# safety_assistant_sch.net
KiCad netlist of a schematic drawn in EAGLE
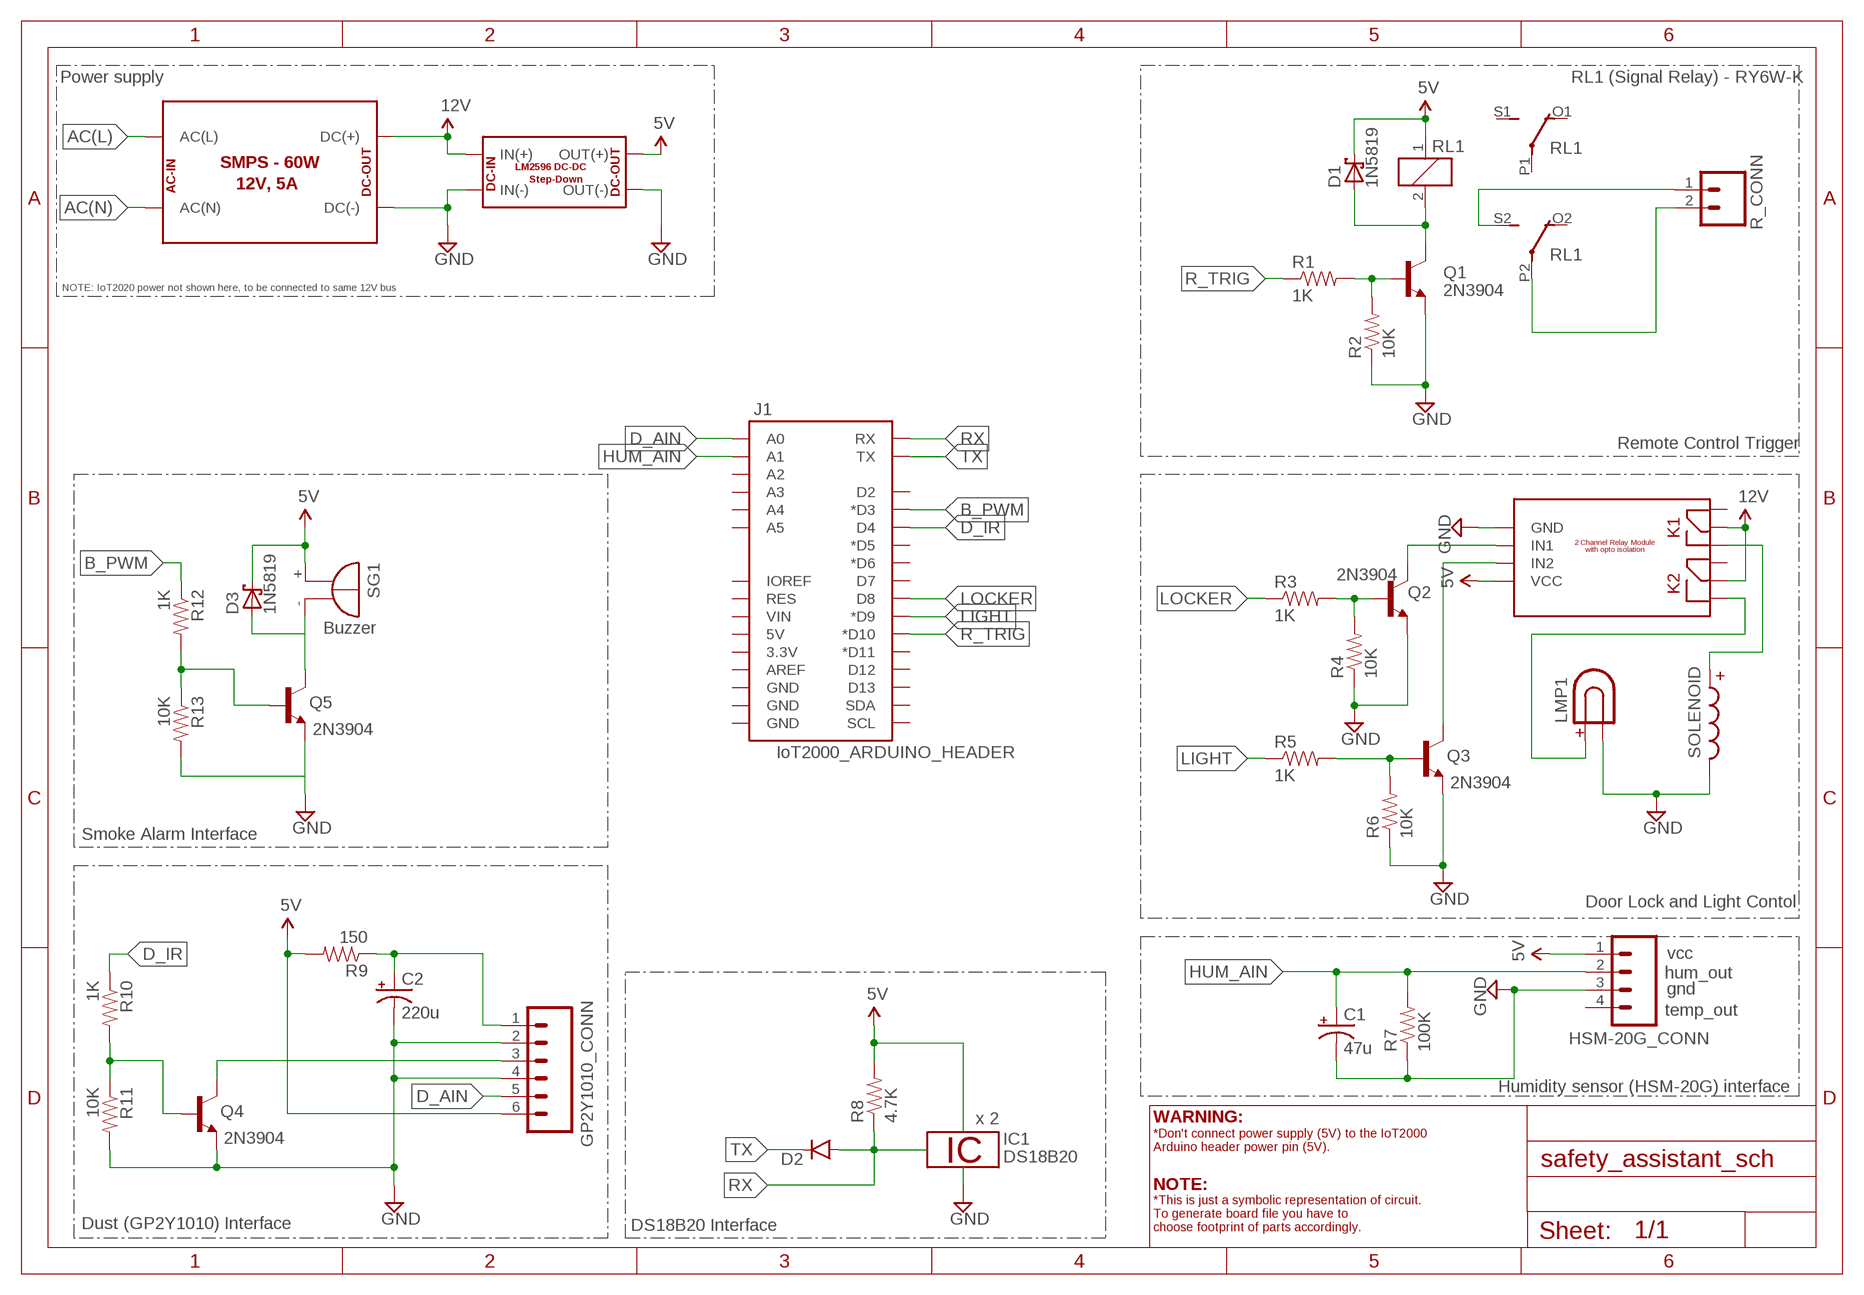
[diagram p0: schematic, sheet 1]

(export (version "E")
  (design (tool "Eeschema 10.0.6"))
  (components
    (comp (ref "C1")
      (value "47u")
      (footprint "eagle-import:CPOL-RADIAL-100UF-25V")
      (libsource (lib "eagle-import") (part "CAP_POLPTH1"))
    )
    (comp (ref "C2")
      (value "220u")
      (footprint "eagle-import:CPOL-RADIAL-100UF-25V")
      (libsource (lib "eagle-import") (part "CAP_POLPTH1"))
    )
    (comp (ref "D1")
      (value "1N5819")
      (footprint "eagle-import:DO41-7.6")
      (libsource (lib "eagle-import") (part "1N5819-B"))
    )
    (comp (ref "D2")
      (value "DIODE1N4148")
      (footprint "eagle-import:DIODE-1N4148")
      (libsource (lib "eagle-import") (part "DIODE1N4148"))
    )
    (comp (ref "D3")
      (value "1N5819")
      (footprint "eagle-import:DO41-7.6")
      (libsource (lib "eagle-import") (part "1N5819-B"))
    )
    (comp (ref "GP2Y1010_CONN")
      (value "M06SILK_FEMALE_PTH")
      (footprint "eagle-import:1X06")
      (libsource (lib "eagle-import") (part "M06SILK_FEMALE_PTH"))
    )
    (comp (ref "HSM-20G_CONN")
      (value "M04POLAR")
      (footprint "eagle-import:MOLEX-1X4")
      (libsource (lib "eagle-import") (part "M04POLAR"))
    )
    (comp (ref "IC1")
      (value "DS18B20")
      (footprint "eagle-import:TO92-")
      (libsource (lib "eagle-import") (part "DS18S20"))
    )
    (comp (ref "J1")
      (value "IoT2000_ARDUINO_HEADER")
      (footprint "eagle-import:UNO_R3_SHIELD")
      (libsource (lib "eagle-import") (part "ARDUINO_R3_SHIELD"))
    )
    (comp (ref "LMP1")
      (value "LAMP")
      (footprint "eagle-import:LDH-5R")
      (libsource (lib "eagle-import") (part "LAMP"))
    )
    (comp (ref "Q1")
      (value "2N3904")
      (footprint "eagle-import:TO-92-AMMO")
      (libsource (lib "eagle-import") (part "TRANSISTOR_NPNBC547"))
    )
    (comp (ref "Q2")
      (value "2N3904")
      (footprint "eagle-import:TO92")
      (libsource (lib "eagle-import") (part "2N3904"))
    )
    (comp (ref "Q3")
      (value "2N3904")
      (footprint "eagle-import:TO92")
      (libsource (lib "eagle-import") (part "2N3904"))
    )
    (comp (ref "Q4")
      (value "2N3904")
      (footprint "eagle-import:TO92")
      (libsource (lib "eagle-import") (part "2N3904"))
    )
    (comp (ref "Q5")
      (value "2N3904")
      (footprint "eagle-import:TO92")
      (libsource (lib "eagle-import") (part "2N3904"))
    )
    (comp (ref "R1")
      (value "1K")
      (footprint "eagle-import:AXIAL-0.3")
      (libsource (lib "eagle-import") (part "RESISTORAXIAL-0.3"))
    )
    (comp (ref "R2")
      (value "10K")
      (footprint "eagle-import:AXIAL-0.3")
      (libsource (lib "eagle-import") (part "RESISTORAXIAL-0.3"))
    )
    (comp (ref "R3")
      (value "1K")
      (footprint "eagle-import:AXIAL-0.3")
      (libsource (lib "eagle-import") (part "RESISTORAXIAL-0.3"))
    )
    (comp (ref "R4")
      (value "10K")
      (footprint "eagle-import:AXIAL-0.3")
      (libsource (lib "eagle-import") (part "RESISTORAXIAL-0.3"))
    )
    (comp (ref "R5")
      (value "1K")
      (footprint "eagle-import:AXIAL-0.3")
      (libsource (lib "eagle-import") (part "RESISTORAXIAL-0.3"))
    )
    (comp (ref "R6")
      (value "10K")
      (footprint "eagle-import:AXIAL-0.3")
      (libsource (lib "eagle-import") (part "RESISTORAXIAL-0.3"))
    )
    (comp (ref "R7")
      (value "100K")
      (footprint "eagle-import:AXIAL-0.3")
      (libsource (lib "eagle-import") (part "RESISTORAXIAL-0.3"))
    )
    (comp (ref "R8")
      (value "4.7K")
      (footprint "eagle-import:AXIAL-0.3")
      (libsource (lib "eagle-import") (part "RESISTORAXIAL-0.3"))
    )
    (comp (ref "R9")
      (value "150")
      (footprint "eagle-import:AXIAL-0.3")
      (libsource (lib "eagle-import") (part "RESISTORAXIAL-0.3"))
    )
    (comp (ref "R10")
      (value "1K")
      (footprint "eagle-import:AXIAL-0.3")
      (libsource (lib "eagle-import") (part "RESISTORAXIAL-0.3"))
    )
    (comp (ref "R11")
      (value "10K")
      (footprint "eagle-import:AXIAL-0.3")
      (libsource (lib "eagle-import") (part "RESISTORAXIAL-0.3"))
    )
    (comp (ref "R12")
      (value "1K")
      (footprint "eagle-import:AXIAL-0.3")
      (libsource (lib "eagle-import") (part "RESISTORAXIAL-0.3"))
    )
    (comp (ref "R13")
      (value "10K")
      (footprint "eagle-import:AXIAL-0.3")
      (libsource (lib "eagle-import") (part "RESISTORAXIAL-0.3"))
    )
    (comp (ref "RL1")
      (value "RY6W-R")
      (footprint "eagle-import:G2R2")
      (fields (field (name "MF") "OMRON COMPONENTS USA") (field (name "MPN") "G2R-2-DC6"))
      (libsource (lib "eagle-import") (part "G2R2"))
    )
    (comp (ref "R_CONN")
      (value "M02PTH")
      (footprint "eagle-import:1X02")
      (libsource (lib "eagle-import") (part "M02PTH"))
    )
    (comp (ref "SG1")
      (value "Buzzer")
      (footprint "eagle-import:EB2505")
      (libsource (lib "eagle-import") (part "EB2505"))
    )
    (comp (ref "SOLENOID")
      (value "L-US0204/7")
      (footprint "eagle-import:0204_7")
      (libsource (lib "eagle-import") (part "L-US0204/7"))
    )
    (comp (ref "U$1")
      (value "RELAY_MODULE")
      (footprint "eagle-import:RELAY_MODULE")
      (libsource (lib "eagle-import") (part "RELAY_MODULE"))
    )
    (comp (ref "U$2")
      (value "LM2596_M")
      (footprint "eagle-import:LM2596_M")
      (libsource (lib "eagle-import") (part "LM2596_M"))
    )
    (comp (ref "U$3")
      (value "SMPS_60W")
      (footprint "eagle-import:SMPS_60W")
      (libsource (lib "eagle-import") (part "SMPS_60W"))
    )
  )
  (nets
    (net (code "1") (name "/P$5") (class "Default")
      (node (ref "U$1") (pin "P$4") (pinfunction "P$5_P$4") (pintype "power_in"))
    )
    (net (code "2") (name "/P$8") (class "Default")
      (node (ref "U$1") (pin "P$7") (pinfunction "P$8_P$7") (pintype "power_in"))
    )
    (net (code "3") (name "5V") (class "Default")
      (node (ref "D1") (pin "C") (pinfunction "C_C") (pintype "passive"))
      (node (ref "D3") (pin "C") (pinfunction "C_C") (pintype "passive"))
      (node (ref "GP2Y1010_CONN") (pin "6") (pinfunction "6_6") (pintype "passive"))
      (node (ref "HSM-20G_CONN") (pin "1") (pinfunction "1_1") (pintype "passive"))
      (node (ref "R8") (pin "P$2") (pinfunction "2_P$2") (pintype "passive"))
      (node (ref "R9") (pin "P$2") (pinfunction "2_P$2") (pintype "passive"))
      (node (ref "RL1") (pin "1") (pinfunction "1_1") (pintype "passive"))
      (node (ref "SG1") (pin "+") (pinfunction "+_+") (pintype "passive"))
      (node (ref "U$1") (pin "P$10") (pinfunction "VCC_P$10") (pintype "power_in"))
      (node (ref "U$2") (pin "P$3") (pinfunction "OUT(+)_P$3") (pintype "power_in"))
    )
    (net (code "4") (name "12V") (class "Default")
      (node (ref "U$1") (pin "P$5") (pinfunction "P$6_P$5") (pintype "power_in"))
      (node (ref "U$1") (pin "P$8") (pinfunction "P$9_P$8") (pintype "power_in"))
      (node (ref "U$2") (pin "P$1") (pinfunction "IN(+)_P$1") (pintype "power_in"))
      (node (ref "U$3") (pin "P$3") (pinfunction "DC(+)_P$3") (pintype "power_in"))
    )
    (net (code "5") (name "AC(L)") (class "Default")
      (node (ref "U$3") (pin "P$1") (pinfunction "AC(L)_P$1") (pintype "power_in"))
    )
    (net (code "6") (name "AC(N)") (class "Default")
      (node (ref "U$3") (pin "P$2") (pinfunction "AC(N)_P$2") (pintype "power_in"))
    )
    (net (code "7") (name "B_PWM") (class "Default")
      (node (ref "J1") (pin "D3") (pinfunction "*D3_D3") (pintype "bidirectional"))
      (node (ref "R12") (pin "P$1") (pinfunction "1_P$1") (pintype "passive"))
    )
    (net (code "8") (name "D_AIN") (class "Default")
      (node (ref "GP2Y1010_CONN") (pin "5") (pinfunction "5_5") (pintype "passive"))
      (node (ref "J1") (pin "A0") (pinfunction "A0_A0") (pintype "bidirectional"))
    )
    (net (code "9") (name "D_IR") (class "Default")
      (node (ref "J1") (pin "D4") (pinfunction "D4_D4") (pintype "bidirectional"))
      (node (ref "R10") (pin "P$1") (pinfunction "1_P$1") (pintype "passive"))
    )
    (net (code "10") (name "GND") (class "Default")
      (node (ref "C1") (pin "2") (pinfunction "-_2") (pintype "passive"))
      (node (ref "C2") (pin "2") (pinfunction "-_2") (pintype "passive"))
      (node (ref "GP2Y1010_CONN") (pin "2") (pinfunction "2_2") (pintype "passive"))
      (node (ref "GP2Y1010_CONN") (pin "4") (pinfunction "4_4") (pintype "passive"))
      (node (ref "HSM-20G_CONN") (pin "3") (pinfunction "3_3") (pintype "passive"))
      (node (ref "LMP1") (pin "2") (pinfunction "2_2") (pintype "passive"))
      (node (ref "Q1") (pin "3") (pinfunction "E_3") (pintype "passive"))
      (node (ref "Q2") (pin "3") (pinfunction "E_3") (pintype "passive"))
      (node (ref "Q3") (pin "3") (pinfunction "E_3") (pintype "passive"))
      (node (ref "Q4") (pin "3") (pinfunction "E_3") (pintype "passive"))
      (node (ref "Q5") (pin "3") (pinfunction "E_3") (pintype "passive"))
      (node (ref "R11") (pin "P$2") (pinfunction "2_P$2") (pintype "passive"))
      (node (ref "R13") (pin "P$2") (pinfunction "2_P$2") (pintype "passive"))
      (node (ref "R2") (pin "P$1") (pinfunction "1_P$1") (pintype "passive"))
      (node (ref "R4") (pin "P$1") (pinfunction "1_P$1") (pintype "passive"))
      (node (ref "R6") (pin "P$1") (pinfunction "1_P$1") (pintype "passive"))
      (node (ref "R7") (pin "P$1") (pinfunction "1_P$1") (pintype "passive"))
      (node (ref "SOLENOID") (pin "2") (pinfunction "2_2") (pintype "passive"))
      (node (ref "U$1") (pin "P$1") (pinfunction "GND_P$1") (pintype "power_in"))
      (node (ref "U$2") (pin "P$2") (pinfunction "IN(-)_P$2") (pintype "power_in"))
      (node (ref "U$2") (pin "P$4") (pinfunction "OUT(-)_P$4") (pintype "power_in"))
      (node (ref "U$3") (pin "P$4") (pinfunction "DC(-)_P$4") (pintype "power_in"))
    )
    (net (code "11") (name "HUM_AIN") (class "Default")
      (node (ref "C1") (pin "1") (pinfunction "+_1") (pintype "passive"))
      (node (ref "HSM-20G_CONN") (pin "2") (pinfunction "2_2") (pintype "passive"))
      (node (ref "J1") (pin "A1") (pinfunction "A1_A1") (pintype "bidirectional"))
      (node (ref "R7") (pin "P$2") (pinfunction "2_P$2") (pintype "passive"))
    )
    (net (code "12") (name "LIGHT") (class "Default")
      (node (ref "J1") (pin "D9") (pinfunction "*D9_D9") (pintype "bidirectional"))
      (node (ref "R5") (pin "P$1") (pinfunction "1_P$1") (pintype "passive"))
    )
    (net (code "13") (name "LOCKER") (class "Default")
      (node (ref "J1") (pin "D8") (pinfunction "D8_D8") (pintype "bidirectional"))
      (node (ref "R3") (pin "P$1") (pinfunction "1_P$1") (pintype "passive"))
    )
    (net (code "14") (name "Net-(C2-+)") (class "Default")
      (node (ref "C2") (pin "1") (pinfunction "+_1") (pintype "passive"))
      (node (ref "GP2Y1010_CONN") (pin "1") (pinfunction "1_1") (pintype "passive"))
      (node (ref "R9") (pin "P$1") (pinfunction "1_P$1") (pintype "passive"))
    )
    (net (code "15") (name "Net-(Q1-B)") (class "Default")
      (node (ref "Q1") (pin "2") (pinfunction "B_2") (pintype "passive"))
      (node (ref "R1") (pin "P$2") (pinfunction "2_P$2") (pintype "passive"))
      (node (ref "R2") (pin "P$2") (pinfunction "2_P$2") (pintype "passive"))
    )
    (net (code "16") (name "Net-(Q1-C)") (class "Default")
      (node (ref "D1") (pin "A") (pinfunction "A_A") (pintype "passive"))
      (node (ref "Q1") (pin "1") (pinfunction "C_1") (pintype "passive"))
      (node (ref "RL1") (pin "2") (pinfunction "2_2") (pintype "passive"))
    )
    (net (code "17") (name "Net-(Q2-B)") (class "Default")
      (node (ref "Q2") (pin "2") (pinfunction "B_2") (pintype "passive"))
      (node (ref "R3") (pin "P$2") (pinfunction "2_P$2") (pintype "passive"))
      (node (ref "R4") (pin "P$2") (pinfunction "2_P$2") (pintype "passive"))
    )
    (net (code "18") (name "Net-(Q2-C)") (class "Default")
      (node (ref "Q2") (pin "1") (pinfunction "C_1") (pintype "passive"))
      (node (ref "U$1") (pin "P$2") (pinfunction "IN1_P$2") (pintype "bidirectional"))
    )
    (net (code "19") (name "Net-(Q3-B)") (class "Default")
      (node (ref "Q3") (pin "2") (pinfunction "B_2") (pintype "passive"))
      (node (ref "R5") (pin "P$2") (pinfunction "2_P$2") (pintype "passive"))
      (node (ref "R6") (pin "P$2") (pinfunction "2_P$2") (pintype "passive"))
    )
    (net (code "20") (name "Net-(Q3-C)") (class "Default")
      (node (ref "Q3") (pin "1") (pinfunction "C_1") (pintype "passive"))
      (node (ref "U$1") (pin "P$3") (pinfunction "IN2_P$3") (pintype "bidirectional"))
    )
    (net (code "21") (name "Net-(Q4-B)") (class "Default")
      (node (ref "Q4") (pin "2") (pinfunction "B_2") (pintype "passive"))
      (node (ref "R10") (pin "P$2") (pinfunction "2_P$2") (pintype "passive"))
      (node (ref "R11") (pin "P$1") (pinfunction "1_P$1") (pintype "passive"))
    )
    (net (code "22") (name "Net-(Q4-C)") (class "Default")
      (node (ref "GP2Y1010_CONN") (pin "3") (pinfunction "3_3") (pintype "passive"))
      (node (ref "Q4") (pin "1") (pinfunction "C_1") (pintype "passive"))
    )
    (net (code "23") (name "Net-(Q5-B)") (class "Default")
      (node (ref "Q5") (pin "2") (pinfunction "B_2") (pintype "passive"))
      (node (ref "R12") (pin "P$2") (pinfunction "2_P$2") (pintype "passive"))
      (node (ref "R13") (pin "P$1") (pinfunction "1_P$1") (pintype "passive"))
    )
    (net (code "24") (name "Net-(Q5-C)") (class "Default")
      (node (ref "D3") (pin "A") (pinfunction "A_A") (pintype "passive"))
      (node (ref "Q5") (pin "1") (pinfunction "C_1") (pintype "passive"))
      (node (ref "SG1") (pin "-") (pinfunction "-_-") (pintype "passive"))
    )
    (net (code "25") (name "Net-(RL1C-P)") (class "Default")
      (node (ref "RL1") (pin "P2") (pinfunction "P_P2") (pintype "passive"))
      (node (ref "R_CONN") (pin "2") (pinfunction "2_2") (pintype "passive"))
    )
    (net (code "26") (name "Net-(RL1C-S)") (class "Default")
      (node (ref "RL1") (pin "S2") (pinfunction "S_S2") (pintype "passive"))
      (node (ref "R_CONN") (pin "1") (pinfunction "1_1") (pintype "passive"))
    )
    (net (code "27") (name "Net-(U$1-P$7)") (class "Default")
      (node (ref "SOLENOID") (pin "1") (pinfunction "1_1") (pintype "passive"))
      (node (ref "U$1") (pin "P$6") (pinfunction "P$7_P$6") (pintype "power_in"))
    )
    (net (code "28") (name "Net-(U$1-P$10)") (class "Default")
      (node (ref "LMP1") (pin "1") (pinfunction "1_1") (pintype "passive"))
      (node (ref "U$1") (pin "P$9") (pinfunction "P$10_P$9") (pintype "power_in"))
    )
    (net (code "29") (name "RX") (class "Default")
      (node (ref "D2") (pin "A") (pinfunction "A_A") (pintype "passive"))
      (node (ref "J1") (pin "RX") (pinfunction "RX_RX") (pintype "bidirectional"))
      (node (ref "R8") (pin "P$1") (pinfunction "1_P$1") (pintype "passive"))
    )
    (net (code "30") (name "R_TRIG") (class "Default")
      (node (ref "J1") (pin "D10") (pinfunction "*D10_D10") (pintype "bidirectional"))
      (node (ref "R1") (pin "P$1") (pinfunction "1_P$1") (pintype "passive"))
    )
    (net (code "31") (name "TX") (class "Default")
      (node (ref "D2") (pin "C") (pinfunction "C_C") (pintype "passive"))
      (node (ref "J1") (pin "TX") (pinfunction "TX_TX") (pintype "bidirectional"))
    )
    (net (code "32") (name "unconnected-(HSM-20G_CONN-Pad4)") (class "Default")
      (node (ref "HSM-20G_CONN") (pin "4") (pinfunction "4_4") (pintype "passive"))
    )
    (net (code "33") (name "unconnected-(J1-*D5-PadD5)") (class "Default")
      (node (ref "J1") (pin "D5") (pinfunction "*D5_D5") (pintype "bidirectional"))
    )
    (net (code "34") (name "unconnected-(J1-*D6-PadD6)") (class "Default")
      (node (ref "J1") (pin "D6") (pinfunction "*D6_D6") (pintype "bidirectional"))
    )
    (net (code "35") (name "unconnected-(J1-*D11-PadD11)") (class "Default")
      (node (ref "J1") (pin "D11") (pinfunction "*D11_D11") (pintype "bidirectional"))
    )
    (net (code "36") (name "unconnected-(J1-GND-PadGND@0)") (class "Default")
      (node (ref "J1") (pin "GND@0") (pinfunction "GND_GND@0") (pintype "bidirectional"))
    )
    (net (code "37") (name "unconnected-(J1-GND-PadGND@1)") (class "Default")
      (node (ref "J1") (pin "GND@1") (pinfunction "GND_GND@1") (pintype "bidirectional"))
    )
    (net (code "38") (name "unconnected-(J1-GND-PadGND@2)") (class "Default")
      (node (ref "J1") (pin "GND@2") (pinfunction "GND_GND@2") (pintype "bidirectional"))
    )
    (net (code "39") (name "unconnected-(J1-Pad3.3V)") (class "Default")
      (node (ref "J1") (pin "3.3V") (pinfunction "3.3V_3.3V") (pintype "bidirectional"))
    )
    (net (code "40") (name "unconnected-(J1-Pad5V)") (class "Default")
      (node (ref "J1") (pin "5V") (pinfunction "5V_5V") (pintype "bidirectional"))
    )
    (net (code "41") (name "unconnected-(J1-PadA2)") (class "Default")
      (node (ref "J1") (pin "A2") (pinfunction "A2_A2") (pintype "bidirectional"))
    )
    (net (code "42") (name "unconnected-(J1-PadA3)") (class "Default")
      (node (ref "J1") (pin "A3") (pinfunction "A3_A3") (pintype "bidirectional"))
    )
    (net (code "43") (name "unconnected-(J1-PadA4)") (class "Default")
      (node (ref "J1") (pin "A4") (pinfunction "A4_A4") (pintype "bidirectional"))
    )
    (net (code "44") (name "unconnected-(J1-PadA5)") (class "Default")
      (node (ref "J1") (pin "A5") (pinfunction "A5_A5") (pintype "bidirectional"))
    )
    (net (code "45") (name "unconnected-(J1-PadAREF)") (class "Default")
      (node (ref "J1") (pin "AREF") (pinfunction "AREF_AREF") (pintype "bidirectional"))
    )
    (net (code "46") (name "unconnected-(J1-PadD2)") (class "Default")
      (node (ref "J1") (pin "D2") (pinfunction "D2_D2") (pintype "bidirectional"))
    )
    (net (code "47") (name "unconnected-(J1-PadD7)") (class "Default")
      (node (ref "J1") (pin "D7") (pinfunction "D7_D7") (pintype "bidirectional"))
    )
    (net (code "48") (name "unconnected-(J1-PadD12)") (class "Default")
      (node (ref "J1") (pin "D12") (pinfunction "D12_D12") (pintype "bidirectional"))
    )
    (net (code "49") (name "unconnected-(J1-PadD13)") (class "Default")
      (node (ref "J1") (pin "D13") (pinfunction "D13_D13") (pintype "bidirectional"))
    )
    (net (code "50") (name "unconnected-(J1-PadIOREF)") (class "Default")
      (node (ref "J1") (pin "IOREF") (pinfunction "IOREF_IOREF") (pintype "bidirectional"))
    )
    (net (code "51") (name "unconnected-(J1-PadRES)") (class "Default")
      (node (ref "J1") (pin "RES") (pinfunction "RES_RES") (pintype "bidirectional"))
    )
    (net (code "52") (name "unconnected-(J1-PadSCL)") (class "Default")
      (node (ref "J1") (pin "SCL") (pinfunction "SCL_SCL") (pintype "bidirectional"))
    )
    (net (code "53") (name "unconnected-(J1-PadSDA)") (class "Default")
      (node (ref "J1") (pin "SDA") (pinfunction "SDA_SDA") (pintype "bidirectional"))
    )
    (net (code "54") (name "unconnected-(J1-PadVIN)") (class "Default")
      (node (ref "J1") (pin "VIN") (pinfunction "VIN_VIN") (pintype "bidirectional"))
    )
    (net (code "55") (name "unconnected-(RL1B-O-PadO1)") (class "Default")
      (node (ref "RL1") (pin "O1") (pinfunction "O_O1") (pintype "passive"))
    )
    (net (code "56") (name "unconnected-(RL1B-P-PadP1)") (class "Default")
      (node (ref "RL1") (pin "P1") (pinfunction "P_P1") (pintype "passive"))
    )
    (net (code "57") (name "unconnected-(RL1B-S-PadS1)") (class "Default")
      (node (ref "RL1") (pin "S1") (pinfunction "S_S1") (pintype "passive"))
    )
    (net (code "58") (name "unconnected-(RL1C-O-PadO2)") (class "Default")
      (node (ref "RL1") (pin "O2") (pinfunction "O_O2") (pintype "passive"))
    )
  )
)
